# USB_JST-XH_Converter.net
KiCad netlist of a schematic drawn in EAGLE
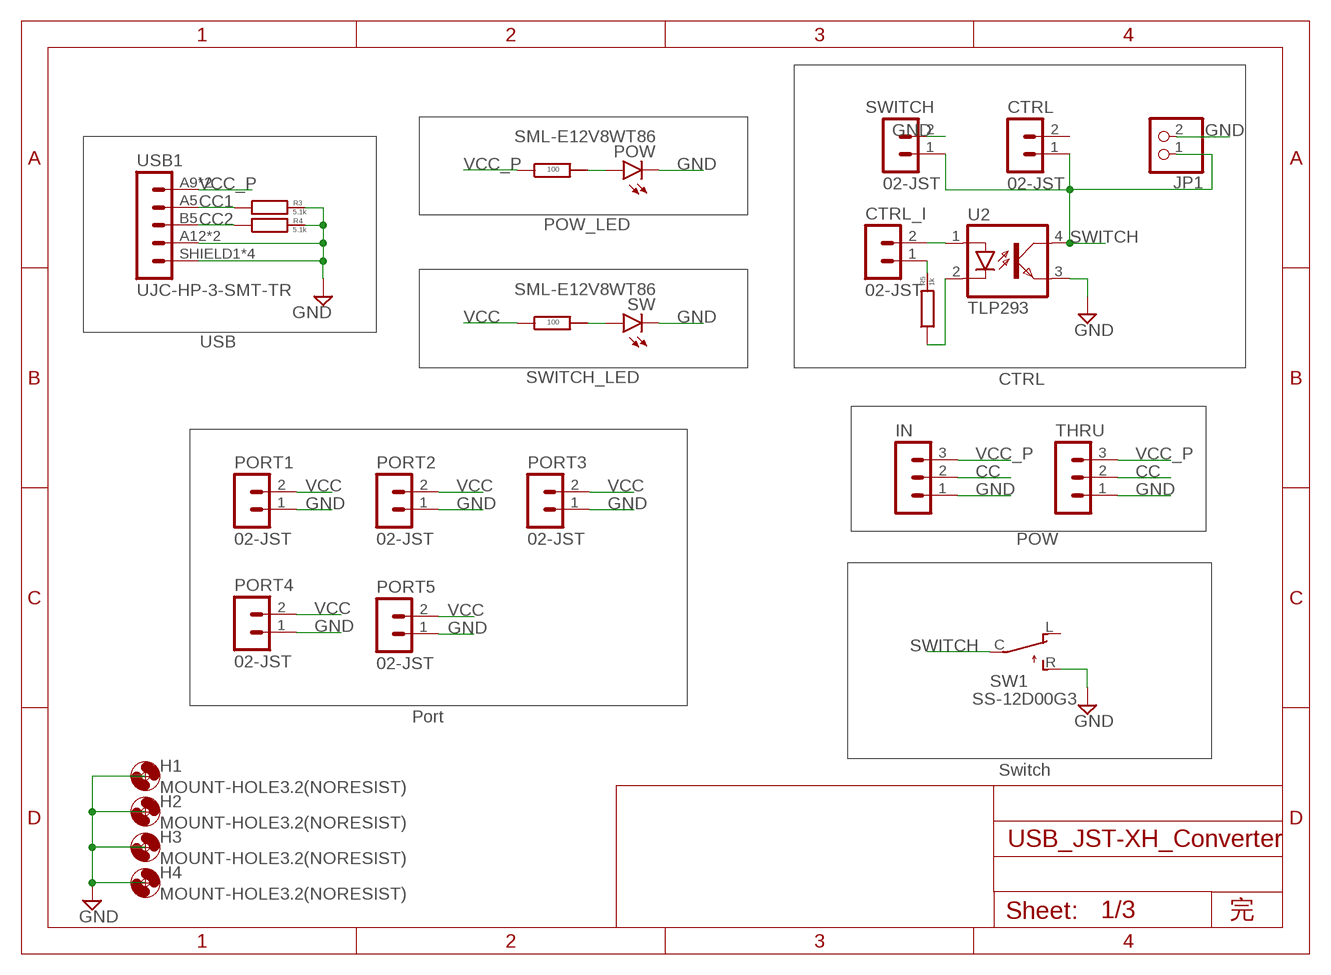
[diagram p0: schematic, sheet 1]
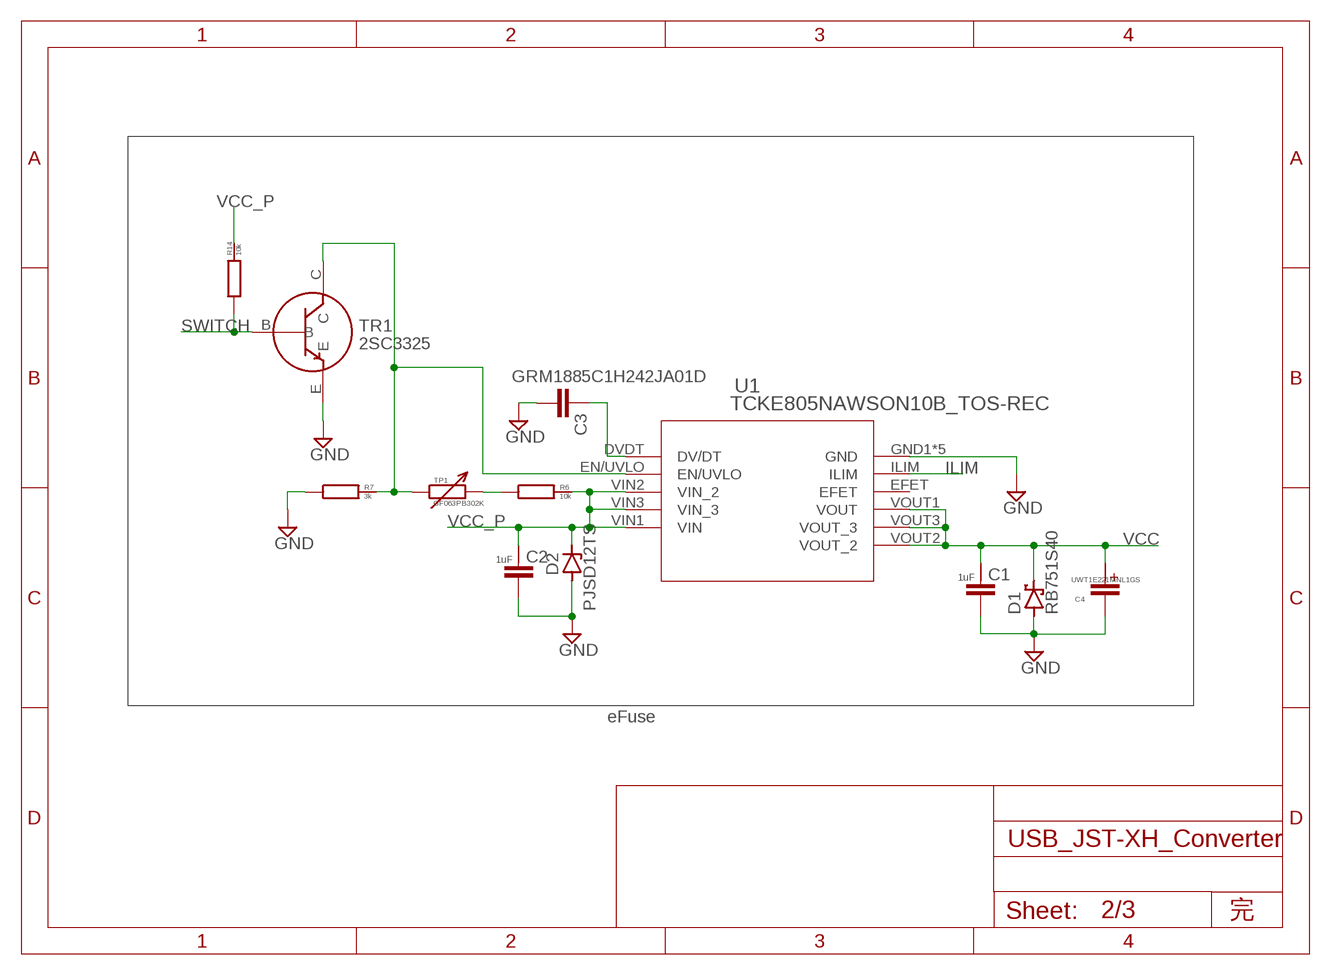
[diagram p1: schematic, sheet 2]
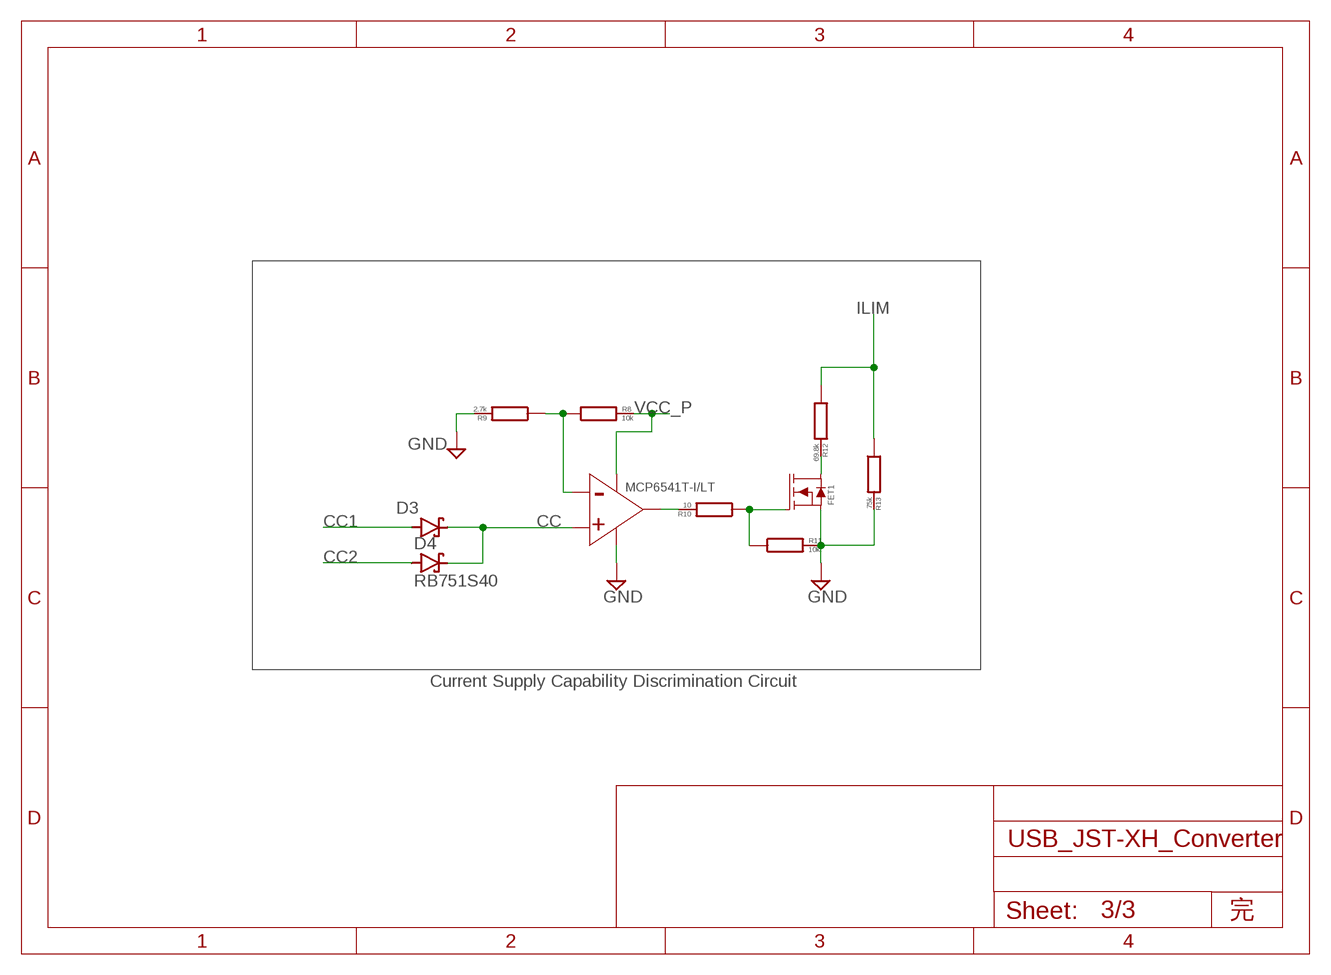
[diagram p2: schematic, sheet 3]

(export (version "E")
  (design (tool "Eeschema 10.0.6"))
  (components
    (comp (ref "COMP1")
      (value "MCP6541T-I/LT")
      (footprint "eagle-import:SC-70-5")
      (libsource (lib "eagle-import") (part "MCP6541T-I/LT"))
    )
    (comp (ref "D3")
      (value "RB751S40")
      (footprint "eagle-import:SOD-523")
      (libsource (lib "eagle-import") (part "RB751S40"))
    )
    (comp (ref "D4")
      (value "RB751S40")
      (footprint "eagle-import:SOD-523")
      (libsource (lib "eagle-import") (part "RB751S40"))
    )
    (comp (ref "FET1")
      (value "BSS138")
      (footprint "eagle-import:SOT-23")
      (libsource (lib "eagle-import") (part "BSS138"))
    )
    (comp (ref "R8")
      (value "10k")
      (footprint "eagle-import:RG2012")
      (libsource (lib "eagle-import") (part "RG2012"))
    )
    (comp (ref "R9")
      (value "2.7k")
      (footprint "eagle-import:RG2012")
      (libsource (lib "eagle-import") (part "RG2012"))
    )
    (comp (ref "R10")
      (value "10")
      (footprint "eagle-import:RG2012")
      (libsource (lib "eagle-import") (part "RG2012"))
    )
    (comp (ref "R11")
      (value "10k")
      (footprint "eagle-import:RG2012")
      (libsource (lib "eagle-import") (part "RG2012"))
    )
    (comp (ref "R12")
      (value "69.8k")
      (footprint "eagle-import:RG2012")
      (libsource (lib "eagle-import") (part "RG2012"))
    )
    (comp (ref "R13")
      (value "75k")
      (footprint "eagle-import:RG2012")
      (libsource (lib "eagle-import") (part "RG2012"))
    )
    (comp (ref "CTRL")
      (value "02-JST")
      (footprint "eagle-import:B2B-XH")
      (libsource (lib "eagle-import") (part "02-JST"))
    )
    (comp (ref "CTRL_I")
      (value "02-JST")
      (footprint "eagle-import:B2B-XH")
      (libsource (lib "eagle-import") (part "02-JST"))
    )
    (comp (ref "H1")
      (value "MOUNT-HOLE3.2(NORESIST)")
      (footprint "eagle-import:3,2")
      (libsource (lib "eagle-import") (part "MOUNT-HOLE3.2(NORESIST)"))
    )
    (comp (ref "H2")
      (value "MOUNT-HOLE3.2(NORESIST)")
      (footprint "eagle-import:3,2")
      (libsource (lib "eagle-import") (part "MOUNT-HOLE3.2(NORESIST)"))
    )
    (comp (ref "H3")
      (value "MOUNT-HOLE3.2(NORESIST)")
      (footprint "eagle-import:3,2")
      (libsource (lib "eagle-import") (part "MOUNT-HOLE3.2(NORESIST)"))
    )
    (comp (ref "H4")
      (value "MOUNT-HOLE3.2(NORESIST)")
      (footprint "eagle-import:3,2")
      (libsource (lib "eagle-import") (part "MOUNT-HOLE3.2(NORESIST)"))
    )
    (comp (ref "IN")
      (value "03-JST")
      (footprint "eagle-import:B3B-XH")
      (libsource (lib "eagle-import") (part "03-JST"))
    )
    (comp (ref "JP1")
      (value "PINHD-1X2")
      (footprint "eagle-import:1X02")
      (libsource (lib "eagle-import") (part "PINHD-1X2"))
    )
    (comp (ref "PORT1")
      (value "02-JST")
      (footprint "eagle-import:B2B-XH")
      (libsource (lib "eagle-import") (part "02-JST"))
    )
    (comp (ref "PORT2")
      (value "02-JST")
      (footprint "eagle-import:B2B-XH")
      (libsource (lib "eagle-import") (part "02-JST"))
    )
    (comp (ref "PORT3")
      (value "02-JST")
      (footprint "eagle-import:B2B-XH")
      (libsource (lib "eagle-import") (part "02-JST"))
    )
    (comp (ref "PORT4")
      (value "02-JST")
      (footprint "eagle-import:B2B-XH")
      (libsource (lib "eagle-import") (part "02-JST"))
    )
    (comp (ref "PORT5")
      (value "02-JST")
      (footprint "eagle-import:B2B-XH")
      (libsource (lib "eagle-import") (part "02-JST"))
    )
    (comp (ref "POW")
      (value "SML-E12V8WT86")
      (footprint "eagle-import:SML-E12V8WT86")
      (libsource (lib "eagle-import") (part "SML-E12V8WT86"))
    )
    (comp (ref "R1")
      (value "RG2012N-101-B-T5")
      (footprint "eagle-import:RG2012")
      (libsource (lib "eagle-import") (part "RG2012N-101-B-T5"))
    )
    (comp (ref "R2")
      (value "RG2012N-101-B-T5")
      (footprint "eagle-import:RG2012")
      (libsource (lib "eagle-import") (part "RG2012N-101-B-T5"))
    )
    (comp (ref "R3")
      (value "5.1k")
      (footprint "eagle-import:RG2012")
      (libsource (lib "eagle-import") (part "RG2012"))
    )
    (comp (ref "R4")
      (value "5.1k")
      (footprint "eagle-import:RG2012")
      (libsource (lib "eagle-import") (part "RG2012"))
    )
    (comp (ref "R5")
      (value "1k")
      (footprint "eagle-import:RG2012")
      (libsource (lib "eagle-import") (part "RG2012"))
    )
    (comp (ref "SW")
      (value "SML-E12V8WT86")
      (footprint "eagle-import:SML-E12V8WT86")
      (libsource (lib "eagle-import") (part "SML-E12V8WT86"))
    )
    (comp (ref "SW1")
      (value "SS-12D00G3")
      (footprint "eagle-import:SS-12D00G3")
      (libsource (lib "eagle-import") (part "SS-12D00G3"))
    )
    (comp (ref "SWITCH")
      (value "02-JST")
      (footprint "eagle-import:B2B-XH")
      (libsource (lib "eagle-import") (part "02-JST"))
    )
    (comp (ref "THRU")
      (value "03-JST")
      (footprint "eagle-import:B3B-XH")
      (libsource (lib "eagle-import") (part "03-JST"))
    )
    (comp (ref "U2")
      (value "TLP293")
      (footprint "eagle-import:SO4_TOS")
      (fields (field (name "COPYRIGHT") "Copyright (C) 2022 Ultra Librarian. All rights reserved."))
      (libsource (lib "eagle-import") (part "TLP293"))
    )
    (comp (ref "USB1")
      (value "UJC-HP-3-SMT-TR")
      (footprint "eagle-import:UJC-HP-3-SMT-TR")
      (libsource (lib "eagle-import") (part "UJC-HP-3-SMT-TR"))
    )
    (comp (ref "C1")
      (value "GRM21BC72A105KE01")
      (footprint "eagle-import:GRM21BC72A105KE01")
      (libsource (lib "eagle-import") (part "GRM21BC72A105KE01"))
    )
    (comp (ref "C2")
      (value "GRM21BC72A105KE01")
      (footprint "eagle-import:GRM21BC72A105KE01")
      (libsource (lib "eagle-import") (part "GRM21BC72A105KE01"))
    )
    (comp (ref "C3")
      (value "GRM1885C1H242JA01D")
      (footprint "eagle-import:GRM18")
      (libsource (lib "eagle-import") (part "GRM1885C1H242JA01D"))
    )
    (comp (ref "C4")
      (value "UWT1E221MNL1GS")
      (footprint "eagle-import:UWT1E221MNL1GS")
      (libsource (lib "eagle-import") (part "UWT1E221MNL1GS"))
    )
    (comp (ref "D1")
      (value "RB751S40")
      (footprint "eagle-import:SOD-523")
      (libsource (lib "eagle-import") (part "RB751S40"))
    )
    (comp (ref "D2")
      (value "PJSD12TS")
      (footprint "eagle-import:SOD-523")
      (libsource (lib "eagle-import") (part "PJSD12TS"))
    )
    (comp (ref "R6")
      (value "10k")
      (footprint "eagle-import:RG2012")
      (libsource (lib "eagle-import") (part "RG2012"))
    )
    (comp (ref "R7")
      (value "3k")
      (footprint "eagle-import:RG2012")
      (libsource (lib "eagle-import") (part "RG2012"))
    )
    (comp (ref "R14")
      (value "10k")
      (footprint "eagle-import:RG2012")
      (libsource (lib "eagle-import") (part "RG2012"))
    )
    (comp (ref "TP1")
      (value "GF063PB302K")
      (footprint "eagle-import:GF063PB104K")
      (libsource (lib "eagle-import") (part "GF063PB302K"))
    )
    (comp (ref "TR1")
      (value "2SC3325")
      (footprint "eagle-import:2SC3325")
      (libsource (lib "eagle-import") (part "2SC3325"))
    )
    (comp (ref "U1")
      (value "TCKE805NAWSON10B_TOS-REC")
      (footprint "eagle-import:WSON10B_TOS-RIC")
      (libsource (lib "eagle-import") (part "TCKE805NAWSON10B_TOS-REC"))
    )
  )
  (nets
    (net (code "1") (name "CC") (class "Default")
      (node (ref "COMP1") (pin "IN+") (pinfunction "IN+_IN+") (pintype "bidirectional"))
      (node (ref "D3") (pin "C") (pinfunction "C_C") (pintype "passive"))
      (node (ref "D4") (pin "C") (pinfunction "C_C") (pintype "passive"))
      (node (ref "IN") (pin "2") (pinfunction "2_2") (pintype "passive"))
      (node (ref "THRU") (pin "2") (pinfunction "2_2") (pintype "passive"))
    )
    (net (code "2") (name "CC1") (class "Default")
      (node (ref "D3") (pin "A") (pinfunction "A_A") (pintype "passive"))
      (node (ref "R3") (pin "LEFT") (pinfunction "LEFT_LEFT") (pintype "bidirectional"))
      (node (ref "USB1") (pin "A5") (pinfunction "CC1_A5") (pintype "passive"))
    )
    (net (code "3") (name "CC2") (class "Default")
      (node (ref "D4") (pin "A") (pinfunction "A_A") (pintype "passive"))
      (node (ref "R4") (pin "LEFT") (pinfunction "LEFT_LEFT") (pintype "bidirectional"))
      (node (ref "USB1") (pin "B5") (pinfunction "CC2_B5") (pintype "passive"))
    )
    (net (code "4") (name "GND") (class "Default")
      (node (ref "C1") (pin "P$2") (pinfunction "P$2_P$2") (pintype "bidirectional"))
      (node (ref "C2") (pin "P$2") (pinfunction "P$2_P$2") (pintype "bidirectional"))
      (node (ref "C3") (pin "R") (pinfunction "2_R") (pintype "passive"))
      (node (ref "C4") (pin "C") (pinfunction "CATHODE_C") (pintype "bidirectional"))
      (node (ref "COMP1") (pin "VSS") (pinfunction "VSS_VSS") (pintype "bidirectional"))
      (node (ref "D1") (pin "A") (pinfunction "A_A") (pintype "passive"))
      (node (ref "D2") (pin "A") (pinfunction "A_A") (pintype "passive"))
      (node (ref "FET1") (pin "S") (pinfunction "S_S") (pintype "passive"))
      (node (ref "H1") (pin "P$1") (pinfunction "P$1_P$1") (pintype "bidirectional"))
      (node (ref "H2") (pin "P$1") (pinfunction "P$1_P$1") (pintype "bidirectional"))
      (node (ref "H3") (pin "P$1") (pinfunction "P$1_P$1") (pintype "bidirectional"))
      (node (ref "H4") (pin "P$1") (pinfunction "P$1_P$1") (pintype "bidirectional"))
      (node (ref "IN") (pin "1") (pinfunction "1_1") (pintype "passive"))
      (node (ref "JP1") (pin "2") (pinfunction "2_2") (pintype "passive"))
      (node (ref "PORT1") (pin "1") (pinfunction "1_1") (pintype "passive"))
      (node (ref "PORT2") (pin "1") (pinfunction "1_1") (pintype "passive"))
      (node (ref "PORT3") (pin "1") (pinfunction "1_1") (pintype "passive"))
      (node (ref "PORT4") (pin "1") (pinfunction "1_1") (pintype "passive"))
      (node (ref "PORT5") (pin "1") (pinfunction "1_1") (pintype "passive"))
      (node (ref "POW") (pin "K") (pinfunction "C_K") (pintype "passive"))
      (node (ref "R11") (pin "RIGHT") (pinfunction "RIGHT_RIGHT") (pintype "bidirectional"))
      (node (ref "R13") (pin "RIGHT") (pinfunction "RIGHT_RIGHT") (pintype "bidirectional"))
      (node (ref "R3") (pin "RIGHT") (pinfunction "RIGHT_RIGHT") (pintype "bidirectional"))
      (node (ref "R4") (pin "RIGHT") (pinfunction "RIGHT_RIGHT") (pintype "bidirectional"))
      (node (ref "R7") (pin "LEFT") (pinfunction "LEFT_LEFT") (pintype "bidirectional"))
      (node (ref "R9") (pin "RIGHT") (pinfunction "RIGHT_RIGHT") (pintype "bidirectional"))
      (node (ref "SW") (pin "K") (pinfunction "C_K") (pintype "passive"))
      (node (ref "SW1") (pin "R") (pinfunction "R_R") (pintype "passive"))
      (node (ref "SWITCH") (pin "2") (pinfunction "2_2") (pintype "passive"))
      (node (ref "THRU") (pin "1") (pinfunction "1_1") (pintype "passive"))
      (node (ref "TR1") (pin "E") (pinfunction "E_E") (pintype "bidirectional"))
      (node (ref "U1") (pin "GND1") (pinfunction "GND_GND1") (pintype "passive"))
      (node (ref "U1") (pin "GND2") (pinfunction "GND_GND2") (pintype "passive"))
      (node (ref "U1") (pin "GND3") (pinfunction "GND_GND3") (pintype "passive"))
      (node (ref "U1") (pin "GND4") (pinfunction "GND_GND4") (pintype "passive"))
      (node (ref "U1") (pin "GND5") (pinfunction "GND_GND5") (pintype "passive"))
      (node (ref "U2") (pin "3") (pinfunction "3_3") (pintype "passive"))
      (node (ref "USB1") (pin "A12") (pinfunction "GND_A12") (pintype "passive"))
      (node (ref "USB1") (pin "B12") (pinfunction "GND_B12") (pintype "passive"))
      (node (ref "USB1") (pin "SHIELD1") (pinfunction "SHIELD_SHIELD1") (pintype "passive"))
      (node (ref "USB1") (pin "SHIELD2") (pinfunction "SHIELD_SHIELD2") (pintype "passive"))
      (node (ref "USB1") (pin "SHIELD3") (pinfunction "SHIELD_SHIELD3") (pintype "passive"))
      (node (ref "USB1") (pin "SHIELD4") (pinfunction "SHIELD_SHIELD4") (pintype "passive"))
    )
    (net (code "5") (name "ILIM") (class "Default")
      (node (ref "R12") (pin "LEFT") (pinfunction "LEFT_LEFT") (pintype "bidirectional"))
      (node (ref "R13") (pin "LEFT") (pinfunction "LEFT_LEFT") (pintype "bidirectional"))
      (node (ref "U1") (pin "ILIM") (pinfunction "ILIM_ILIM") (pintype "input"))
    )
    (net (code "6") (name "Net-(C3-1)") (class "Default")
      (node (ref "C3") (pin "L") (pinfunction "1_L") (pintype "passive"))
      (node (ref "U1") (pin "DVDT") (pinfunction "DV/DT_DVDT") (pintype "input"))
    )
    (net (code "7") (name "Net-(COMP1-PadIN-)") (class "Default")
      (node (ref "COMP1") (pin "IN-") (pinfunction "IN-_IN-") (pintype "bidirectional"))
      (node (ref "R8") (pin "LEFT") (pinfunction "LEFT_LEFT") (pintype "bidirectional"))
      (node (ref "R9") (pin "LEFT") (pinfunction "LEFT_LEFT") (pintype "bidirectional"))
    )
    (net (code "8") (name "Net-(COMP1-PadOUT)") (class "Default")
      (node (ref "COMP1") (pin "OUT") (pinfunction "OUT_OUT") (pintype "bidirectional"))
      (node (ref "R10") (pin "RIGHT") (pinfunction "RIGHT_RIGHT") (pintype "bidirectional"))
    )
    (net (code "9") (name "Net-(CTRL_I-Pad1)") (class "Default")
      (node (ref "CTRL_I") (pin "1") (pinfunction "1_1") (pintype "passive"))
      (node (ref "R5") (pin "RIGHT") (pinfunction "RIGHT_RIGHT") (pintype "bidirectional"))
    )
    (net (code "10") (name "Net-(CTRL_I-Pad2)") (class "Default")
      (node (ref "CTRL_I") (pin "2") (pinfunction "2_2") (pintype "passive"))
      (node (ref "U2") (pin "1") (pinfunction "1_1") (pintype "passive"))
    )
    (net (code "11") (name "Net-(FET1-PadD)") (class "Default")
      (node (ref "FET1") (pin "D") (pinfunction "D_D") (pintype "passive"))
      (node (ref "R12") (pin "RIGHT") (pinfunction "RIGHT_RIGHT") (pintype "bidirectional"))
    )
    (net (code "12") (name "Net-(FET1-PadG)") (class "Default")
      (node (ref "FET1") (pin "G") (pinfunction "G_G") (pintype "passive"))
      (node (ref "R10") (pin "LEFT") (pinfunction "LEFT_LEFT") (pintype "bidirectional"))
      (node (ref "R11") (pin "LEFT") (pinfunction "LEFT_LEFT") (pintype "bidirectional"))
    )
    (net (code "13") (name "Net-(R1-P$1)") (class "Default")
      (node (ref "POW") (pin "A") (pinfunction "A_A") (pintype "passive"))
      (node (ref "R1") (pin "LEFT") (pinfunction "P$1_LEFT") (pintype "bidirectional"))
    )
    (net (code "14") (name "Net-(R2-P$1)") (class "Default")
      (node (ref "R2") (pin "LEFT") (pinfunction "P$1_LEFT") (pintype "bidirectional"))
      (node (ref "SW") (pin "A") (pinfunction "A_A") (pintype "passive"))
    )
    (net (code "15") (name "Net-(R5-PadLEFT)") (class "Default")
      (node (ref "R5") (pin "LEFT") (pinfunction "LEFT_LEFT") (pintype "bidirectional"))
      (node (ref "U2") (pin "2") (pinfunction "2_2") (pintype "passive"))
    )
    (net (code "16") (name "Net-(R6-PadLEFT)") (class "Default")
      (node (ref "R6") (pin "LEFT") (pinfunction "LEFT_LEFT") (pintype "bidirectional"))
      (node (ref "TP1") (pin "CENTER") (pinfunction "RIGHT_CENTER") (pintype "passive"))
      (node (ref "TP1") (pin "RIGHT") (pinfunction "RIGHT_RIGHT") (pintype "passive"))
    )
    (net (code "17") (name "Net-(R7-PadRIGHT)") (class "Default")
      (node (ref "R7") (pin "RIGHT") (pinfunction "RIGHT_RIGHT") (pintype "bidirectional"))
      (node (ref "TP1") (pin "LEFT") (pinfunction "LEFT_LEFT") (pintype "passive"))
      (node (ref "TR1") (pin "C") (pinfunction "C_C") (pintype "bidirectional"))
      (node (ref "U1") (pin "EN/UVLO") (pinfunction "EN/UVLO_EN/UVLO") (pintype "passive"))
    )
    (net (code "18") (name "SWITCH") (class "Default")
      (node (ref "CTRL") (pin "1") (pinfunction "1_1") (pintype "passive"))
      (node (ref "JP1") (pin "1") (pinfunction "1_1") (pintype "passive"))
      (node (ref "R14") (pin "LEFT") (pinfunction "LEFT_LEFT") (pintype "bidirectional"))
      (node (ref "SW1") (pin "C") (pinfunction "C_C") (pintype "passive"))
      (node (ref "SWITCH") (pin "1") (pinfunction "1_1") (pintype "passive"))
      (node (ref "TR1") (pin "B") (pinfunction "B_B") (pintype "bidirectional"))
      (node (ref "U2") (pin "4") (pinfunction "4_4") (pintype "passive"))
    )
    (net (code "19") (name "VCC") (class "Default")
      (node (ref "C1") (pin "P$1") (pinfunction "P$1_P$1") (pintype "bidirectional"))
      (node (ref "C4") (pin "A") (pinfunction "ANODE_A") (pintype "bidirectional"))
      (node (ref "D1") (pin "C") (pinfunction "C_C") (pintype "passive"))
      (node (ref "PORT1") (pin "2") (pinfunction "2_2") (pintype "passive"))
      (node (ref "PORT2") (pin "2") (pinfunction "2_2") (pintype "passive"))
      (node (ref "PORT3") (pin "2") (pinfunction "2_2") (pintype "passive"))
      (node (ref "PORT4") (pin "2") (pinfunction "2_2") (pintype "passive"))
      (node (ref "PORT5") (pin "2") (pinfunction "2_2") (pintype "passive"))
      (node (ref "R2") (pin "RIGHT") (pinfunction "P$2_RIGHT") (pintype "bidirectional"))
      (node (ref "U1") (pin "VOUT1") (pinfunction "VOUT_VOUT1") (pintype "bidirectional"))
      (node (ref "U1") (pin "VOUT2") (pinfunction "VOUT_2_VOUT2") (pintype "bidirectional"))
      (node (ref "U1") (pin "VOUT3") (pinfunction "VOUT_3_VOUT3") (pintype "bidirectional"))
    )
    (net (code "20") (name "VCC_P") (class "Default")
      (node (ref "C2") (pin "P$1") (pinfunction "P$1_P$1") (pintype "bidirectional"))
      (node (ref "COMP1") (pin "VDD") (pinfunction "VDD_VDD") (pintype "bidirectional"))
      (node (ref "D2") (pin "C") (pinfunction "C_C") (pintype "passive"))
      (node (ref "IN") (pin "3") (pinfunction "3_3") (pintype "passive"))
      (node (ref "R1") (pin "RIGHT") (pinfunction "P$2_RIGHT") (pintype "bidirectional"))
      (node (ref "R14") (pin "RIGHT") (pinfunction "RIGHT_RIGHT") (pintype "bidirectional"))
      (node (ref "R6") (pin "RIGHT") (pinfunction "RIGHT_RIGHT") (pintype "bidirectional"))
      (node (ref "R8") (pin "RIGHT") (pinfunction "RIGHT_RIGHT") (pintype "bidirectional"))
      (node (ref "THRU") (pin "3") (pinfunction "3_3") (pintype "passive"))
      (node (ref "U1") (pin "VIN1") (pinfunction "VIN_VIN1") (pintype "input"))
      (node (ref "U1") (pin "VIN2") (pinfunction "VIN_2_VIN2") (pintype "input"))
      (node (ref "U1") (pin "VIN3") (pinfunction "VIN_3_VIN3") (pintype "input"))
      (node (ref "USB1") (pin "A9") (pinfunction "V-BUS_A9") (pintype "passive"))
      (node (ref "USB1") (pin "B9") (pinfunction "V-BUS_B9") (pintype "passive"))
    )
    (net (code "21") (name "unconnected-(CTRL-Pad2)") (class "Default")
      (node (ref "CTRL") (pin "2") (pinfunction "2_2") (pintype "passive"))
    )
    (net (code "22") (name "unconnected-(SW1-PadL)") (class "Default")
      (node (ref "SW1") (pin "L") (pinfunction "L_L") (pintype "passive"))
    )
    (net (code "23") (name "unconnected-(U1-PadEFET)") (class "Default")
      (node (ref "U1") (pin "EFET") (pinfunction "EFET_EFET") (pintype "passive"))
    )
  )
)
